# Teensy3_2_v2.net
KiCad netlist of a schematic drawn in EAGLE
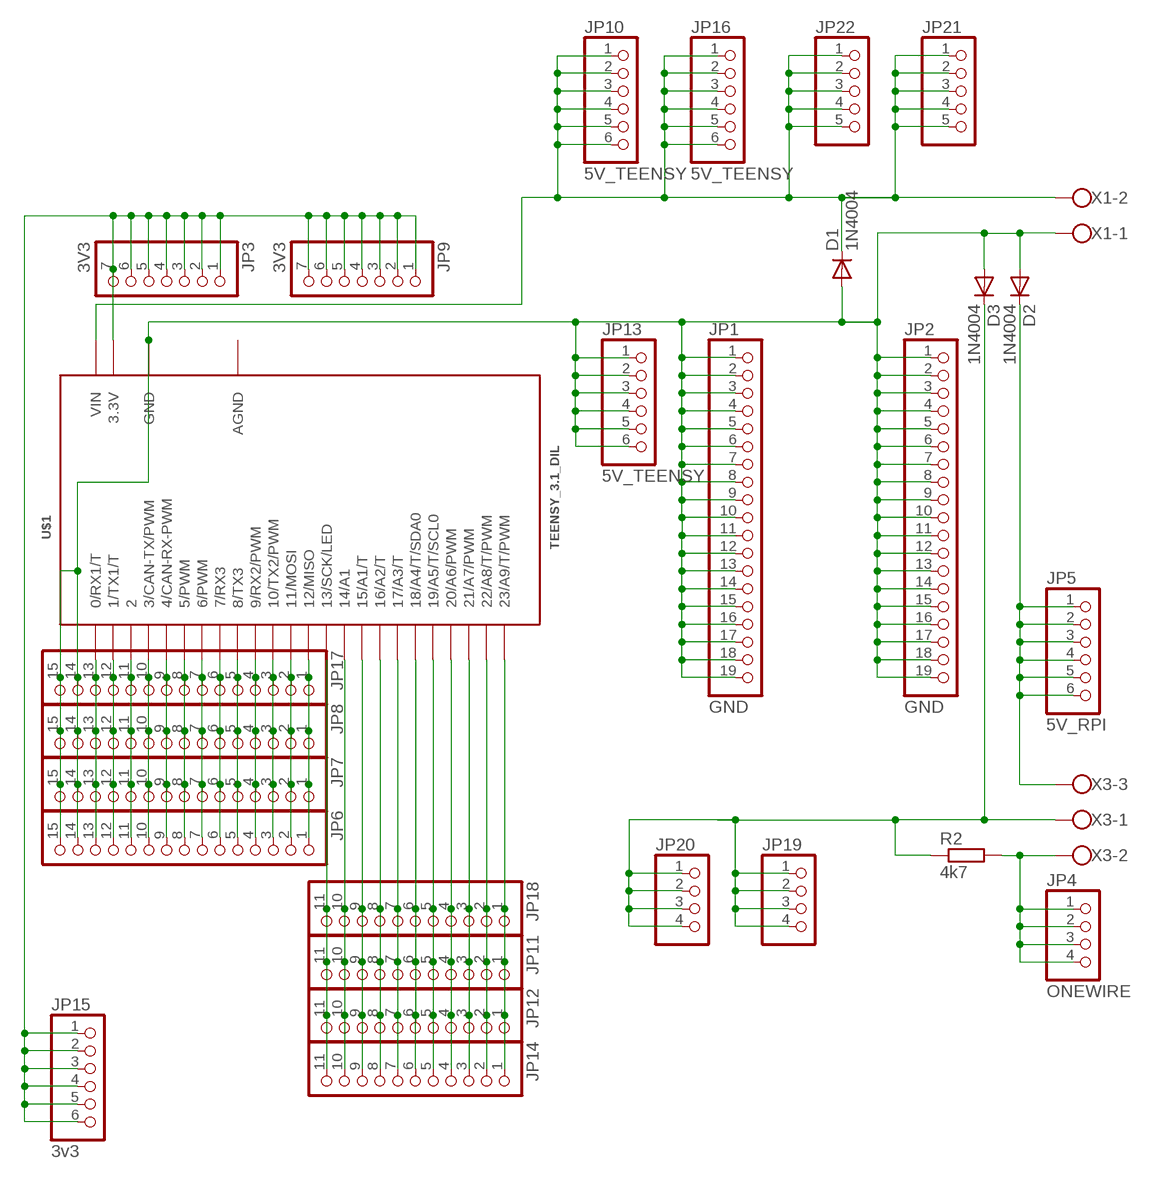
[diagram p0: schematic, sheet 1]

(export (version "E")
  (design (tool "Eeschema 10.0.6"))
  (components
    (comp (ref "D1")
      (value "1N4004")
      (footprint "eagle-import:DO41-10")
      (libsource (lib "eagle-import") (part "1N4004"))
    )
    (comp (ref "D2")
      (value "1N4004")
      (footprint "eagle-import:DO41-10")
      (libsource (lib "eagle-import") (part "1N4004"))
    )
    (comp (ref "D3")
      (value "1N4004")
      (footprint "eagle-import:DO41-10")
      (libsource (lib "eagle-import") (part "1N4004"))
    )
    (comp (ref "JP1")
      (value "GND")
      (footprint "eagle-import:1X19")
      (libsource (lib "eagle-import") (part "PINHD-1X19"))
    )
    (comp (ref "JP2")
      (value "GND")
      (footprint "eagle-import:1X19")
      (libsource (lib "eagle-import") (part "PINHD-1X19"))
    )
    (comp (ref "JP3")
      (value "3V3")
      (footprint "eagle-import:1X07")
      (libsource (lib "eagle-import") (part "PINHD-1X7"))
    )
    (comp (ref "JP4")
      (value "ONEWIRE")
      (footprint "eagle-import:1X04")
      (libsource (lib "eagle-import") (part "PINHD-1X4"))
    )
    (comp (ref "JP5")
      (value "5V_RPI")
      (footprint "eagle-import:1X06")
      (libsource (lib "eagle-import") (part "PINHD-1X6"))
    )
    (comp (ref "JP6")
      (value "PINHD-1X15")
      (footprint "eagle-import:1X15")
      (libsource (lib "eagle-import") (part "PINHD-1X15"))
    )
    (comp (ref "JP7")
      (value "PINHD-1X15")
      (footprint "eagle-import:1X15")
      (libsource (lib "eagle-import") (part "PINHD-1X15"))
    )
    (comp (ref "JP8")
      (value "PINHD-1X15")
      (footprint "eagle-import:1X15")
      (libsource (lib "eagle-import") (part "PINHD-1X15"))
    )
    (comp (ref "JP9")
      (value "3V3")
      (footprint "eagle-import:1X07")
      (libsource (lib "eagle-import") (part "PINHD-1X7"))
    )
    (comp (ref "JP10")
      (value "5V_TEENSY")
      (footprint "eagle-import:1X06")
      (libsource (lib "eagle-import") (part "PINHD-1X6"))
    )
    (comp (ref "JP11")
      (value "PINHD-1X11")
      (footprint "eagle-import:1X11")
      (libsource (lib "eagle-import") (part "PINHD-1X11"))
    )
    (comp (ref "JP12")
      (value "PINHD-1X11")
      (footprint "eagle-import:1X11")
      (libsource (lib "eagle-import") (part "PINHD-1X11"))
    )
    (comp (ref "JP13")
      (value "5V_TEENSY")
      (footprint "eagle-import:1X06")
      (libsource (lib "eagle-import") (part "PINHD-1X6"))
    )
    (comp (ref "JP14")
      (value "PINHD-1X11")
      (footprint "eagle-import:1X11")
      (libsource (lib "eagle-import") (part "PINHD-1X11"))
    )
    (comp (ref "JP15")
      (value "3v3")
      (footprint "eagle-import:1X06")
      (libsource (lib "eagle-import") (part "PINHD-1X6"))
    )
    (comp (ref "JP16")
      (value "5V_TEENSY")
      (footprint "eagle-import:1X06")
      (libsource (lib "eagle-import") (part "PINHD-1X6"))
    )
    (comp (ref "JP17")
      (value "PINHD-1X15")
      (footprint "eagle-import:1X15")
      (libsource (lib "eagle-import") (part "PINHD-1X15"))
    )
    (comp (ref "JP18")
      (value "PINHD-1X11")
      (footprint "eagle-import:1X11")
      (libsource (lib "eagle-import") (part "PINHD-1X11"))
    )
    (comp (ref "JP19")
      (value "PINHD-1X4")
      (footprint "eagle-import:1X04")
      (libsource (lib "eagle-import") (part "PINHD-1X4"))
    )
    (comp (ref "JP20")
      (value "PINHD-1X4")
      (footprint "eagle-import:1X04")
      (libsource (lib "eagle-import") (part "PINHD-1X4"))
    )
    (comp (ref "JP21")
      (value "PINHD-1X5")
      (footprint "eagle-import:1X05")
      (libsource (lib "eagle-import") (part "PINHD-1X5"))
    )
    (comp (ref "JP22")
      (value "PINHD-1X5")
      (footprint "eagle-import:1X05")
      (libsource (lib "eagle-import") (part "PINHD-1X5"))
    )
    (comp (ref "R2")
      (value "4k7")
      (footprint "eagle-import:0204_5")
      (libsource (lib "eagle-import") (part "R-EU_0204/5"))
    )
    (comp (ref "U$1")
      (value "TEENSY_3.1_DIL")
      (footprint "eagle-import:TEENSY3-DIL")
      (libsource (lib "eagle-import") (part "TEENSY_3.1_DIL"))
    )
    (comp (ref "X1")
      (value "W237-102")
      (footprint "eagle-import:W237-102")
      (fields (field (name "MPN") "237-102"))
      (libsource (lib "eagle-import") (part "W237-102"))
    )
    (comp (ref "X3")
      (value "W237-103")
      (footprint "eagle-import:W237-103")
      (fields (field (name "MPN") "237-103"))
      (libsource (lib "eagle-import") (part "W237-103"))
    )
  )
  (nets
    (net (code "1") (name "/AGND") (class "Default")
      (node (ref "U$1") (pin "AGND") (pinfunction "AGND_AGND") (pintype "power_in"))
    )
    (net (code "2") (name "Net-(JP15-Pad1)") (class "Default")
      (node (ref "JP15") (pin "1") (pinfunction "1_1") (pintype "passive"))
      (node (ref "JP15") (pin "2") (pinfunction "2_2") (pintype "passive"))
      (node (ref "JP15") (pin "3") (pinfunction "3_3") (pintype "passive"))
      (node (ref "JP15") (pin "4") (pinfunction "4_4") (pintype "passive"))
      (node (ref "JP15") (pin "5") (pinfunction "5_5") (pintype "passive"))
      (node (ref "JP15") (pin "6") (pinfunction "6_6") (pintype "passive"))
      (node (ref "JP3") (pin "1") (pinfunction "1_1") (pintype "passive"))
      (node (ref "JP3") (pin "2") (pinfunction "2_2") (pintype "passive"))
      (node (ref "JP3") (pin "3") (pinfunction "3_3") (pintype "passive"))
      (node (ref "JP3") (pin "4") (pinfunction "4_4") (pintype "passive"))
      (node (ref "JP3") (pin "5") (pinfunction "5_5") (pintype "passive"))
      (node (ref "JP3") (pin "6") (pinfunction "6_6") (pintype "passive"))
      (node (ref "JP3") (pin "7") (pinfunction "7_7") (pintype "passive"))
      (node (ref "JP9") (pin "1") (pinfunction "1_1") (pintype "passive"))
      (node (ref "JP9") (pin "2") (pinfunction "2_2") (pintype "passive"))
      (node (ref "JP9") (pin "3") (pinfunction "3_3") (pintype "passive"))
      (node (ref "JP9") (pin "4") (pinfunction "4_4") (pintype "passive"))
      (node (ref "JP9") (pin "5") (pinfunction "5_5") (pintype "passive"))
      (node (ref "JP9") (pin "6") (pinfunction "6_6") (pintype "passive"))
      (node (ref "JP9") (pin "7") (pinfunction "7_7") (pintype "passive"))
      (node (ref "U$1") (pin "3.3V") (pinfunction "3.3V_3.3V") (pintype "power_in"))
    )
    (net (code "3") (name "Net-(JP17-Pad11)") (class "Default")
      (node (ref "JP17") (pin "11") (pinfunction "11_11") (pintype "passive"))
      (node (ref "JP6") (pin "11") (pinfunction "11_11") (pintype "passive"))
      (node (ref "JP7") (pin "11") (pinfunction "11_11") (pintype "passive"))
      (node (ref "JP8") (pin "11") (pinfunction "11_11") (pintype "passive"))
      (node (ref "U$1") (pin "2") (pinfunction "2_2") (pintype "bidirectional"))
    )
    (net (code "4") (name "Net-(U$1-0{slash}RX1{slash}T)") (class "Default")
      (node (ref "JP17") (pin "13") (pinfunction "13_13") (pintype "passive"))
      (node (ref "JP6") (pin "13") (pinfunction "13_13") (pintype "passive"))
      (node (ref "JP7") (pin "13") (pinfunction "13_13") (pintype "passive"))
      (node (ref "JP8") (pin "13") (pinfunction "13_13") (pintype "passive"))
      (node (ref "U$1") (pin "0") (pinfunction "0/RX1/T_0") (pintype "bidirectional"))
    )
    (net (code "5") (name "Net-(U$1-1{slash}TX1{slash}T)") (class "Default")
      (node (ref "JP17") (pin "12") (pinfunction "12_12") (pintype "passive"))
      (node (ref "JP6") (pin "12") (pinfunction "12_12") (pintype "passive"))
      (node (ref "JP7") (pin "12") (pinfunction "12_12") (pintype "passive"))
      (node (ref "JP8") (pin "12") (pinfunction "12_12") (pintype "passive"))
      (node (ref "U$1") (pin "1") (pinfunction "1/TX1/T_1") (pintype "bidirectional"))
    )
    (net (code "6") (name "Net-(U$1-3{slash}CAN-TX{slash}PWM)") (class "Default")
      (node (ref "JP17") (pin "10") (pinfunction "10_10") (pintype "passive"))
      (node (ref "JP6") (pin "10") (pinfunction "10_10") (pintype "passive"))
      (node (ref "JP7") (pin "10") (pinfunction "10_10") (pintype "passive"))
      (node (ref "JP8") (pin "10") (pinfunction "10_10") (pintype "passive"))
      (node (ref "U$1") (pin "3") (pinfunction "3/CAN-TX/PWM_3") (pintype "bidirectional"))
    )
    (net (code "7") (name "Net-(U$1-4{slash}CAN-RX-PWM)") (class "Default")
      (node (ref "JP17") (pin "9") (pinfunction "9_9") (pintype "passive"))
      (node (ref "JP6") (pin "9") (pinfunction "9_9") (pintype "passive"))
      (node (ref "JP7") (pin "9") (pinfunction "9_9") (pintype "passive"))
      (node (ref "JP8") (pin "9") (pinfunction "9_9") (pintype "passive"))
      (node (ref "U$1") (pin "4") (pinfunction "4/CAN-RX-PWM_4") (pintype "bidirectional"))
    )
    (net (code "8") (name "Net-(U$1-5{slash}PWM)") (class "Default")
      (node (ref "JP17") (pin "8") (pinfunction "8_8") (pintype "passive"))
      (node (ref "JP6") (pin "8") (pinfunction "8_8") (pintype "passive"))
      (node (ref "JP7") (pin "8") (pinfunction "8_8") (pintype "passive"))
      (node (ref "JP8") (pin "8") (pinfunction "8_8") (pintype "passive"))
      (node (ref "U$1") (pin "5") (pinfunction "5/PWM_5") (pintype "bidirectional"))
    )
    (net (code "9") (name "Net-(U$1-6{slash}PWM)") (class "Default")
      (node (ref "JP17") (pin "7") (pinfunction "7_7") (pintype "passive"))
      (node (ref "JP6") (pin "7") (pinfunction "7_7") (pintype "passive"))
      (node (ref "JP7") (pin "7") (pinfunction "7_7") (pintype "passive"))
      (node (ref "JP8") (pin "7") (pinfunction "7_7") (pintype "passive"))
      (node (ref "U$1") (pin "6") (pinfunction "6/PWM_6") (pintype "bidirectional"))
    )
    (net (code "10") (name "Net-(U$1-7{slash}RX3)") (class "Default")
      (node (ref "JP17") (pin "6") (pinfunction "6_6") (pintype "passive"))
      (node (ref "JP6") (pin "6") (pinfunction "6_6") (pintype "passive"))
      (node (ref "JP7") (pin "6") (pinfunction "6_6") (pintype "passive"))
      (node (ref "JP8") (pin "6") (pinfunction "6_6") (pintype "passive"))
      (node (ref "U$1") (pin "7") (pinfunction "7/RX3_7") (pintype "bidirectional"))
    )
    (net (code "11") (name "Net-(U$1-8{slash}TX3)") (class "Default")
      (node (ref "JP17") (pin "5") (pinfunction "5_5") (pintype "passive"))
      (node (ref "JP6") (pin "5") (pinfunction "5_5") (pintype "passive"))
      (node (ref "JP7") (pin "5") (pinfunction "5_5") (pintype "passive"))
      (node (ref "JP8") (pin "5") (pinfunction "5_5") (pintype "passive"))
      (node (ref "U$1") (pin "8") (pinfunction "8/TX3_8") (pintype "bidirectional"))
    )
    (net (code "12") (name "Net-(U$1-9{slash}RX2{slash}PWM)") (class "Default")
      (node (ref "JP17") (pin "4") (pinfunction "4_4") (pintype "passive"))
      (node (ref "JP6") (pin "4") (pinfunction "4_4") (pintype "passive"))
      (node (ref "JP7") (pin "4") (pinfunction "4_4") (pintype "passive"))
      (node (ref "JP8") (pin "4") (pinfunction "4_4") (pintype "passive"))
      (node (ref "U$1") (pin "9") (pinfunction "9/RX2/PWM_9") (pintype "bidirectional"))
    )
    (net (code "13") (name "Net-(U$1-10{slash}TX2{slash}PWM)") (class "Default")
      (node (ref "JP17") (pin "3") (pinfunction "3_3") (pintype "passive"))
      (node (ref "JP6") (pin "3") (pinfunction "3_3") (pintype "passive"))
      (node (ref "JP7") (pin "3") (pinfunction "3_3") (pintype "passive"))
      (node (ref "JP8") (pin "3") (pinfunction "3_3") (pintype "passive"))
      (node (ref "U$1") (pin "10") (pinfunction "10/TX2/PWM_10") (pintype "bidirectional"))
    )
    (net (code "14") (name "Net-(U$1-11{slash}MOSI)") (class "Default")
      (node (ref "JP17") (pin "2") (pinfunction "2_2") (pintype "passive"))
      (node (ref "JP6") (pin "2") (pinfunction "2_2") (pintype "passive"))
      (node (ref "JP7") (pin "2") (pinfunction "2_2") (pintype "passive"))
      (node (ref "JP8") (pin "2") (pinfunction "2_2") (pintype "passive"))
      (node (ref "U$1") (pin "11") (pinfunction "11/MOSI_11") (pintype "bidirectional"))
    )
    (net (code "15") (name "Net-(U$1-12{slash}MISO)") (class "Default")
      (node (ref "JP17") (pin "1") (pinfunction "1_1") (pintype "passive"))
      (node (ref "JP6") (pin "1") (pinfunction "1_1") (pintype "passive"))
      (node (ref "JP7") (pin "1") (pinfunction "1_1") (pintype "passive"))
      (node (ref "JP8") (pin "1") (pinfunction "1_1") (pintype "passive"))
      (node (ref "U$1") (pin "12") (pinfunction "12/MISO_12") (pintype "bidirectional"))
    )
    (net (code "16") (name "Net-(U$1-13{slash}SCK{slash}LED)") (class "Default")
      (node (ref "JP11") (pin "11") (pinfunction "11_11") (pintype "passive"))
      (node (ref "JP12") (pin "11") (pinfunction "11_11") (pintype "passive"))
      (node (ref "JP14") (pin "11") (pinfunction "11_11") (pintype "passive"))
      (node (ref "JP18") (pin "11") (pinfunction "11_11") (pintype "passive"))
      (node (ref "U$1") (pin "13") (pinfunction "13/SCK/LED_13") (pintype "bidirectional"))
    )
    (net (code "17") (name "Net-(U$1-14{slash}A1)") (class "Default")
      (node (ref "JP11") (pin "10") (pinfunction "10_10") (pintype "passive"))
      (node (ref "JP12") (pin "10") (pinfunction "10_10") (pintype "passive"))
      (node (ref "JP14") (pin "10") (pinfunction "10_10") (pintype "passive"))
      (node (ref "JP18") (pin "10") (pinfunction "10_10") (pintype "passive"))
      (node (ref "U$1") (pin "14/A0") (pinfunction "14/A1_14/A0") (pintype "bidirectional"))
    )
    (net (code "18") (name "Net-(U$1-15{slash}A1{slash}T)") (class "Default")
      (node (ref "JP11") (pin "9") (pinfunction "9_9") (pintype "passive"))
      (node (ref "JP12") (pin "9") (pinfunction "9_9") (pintype "passive"))
      (node (ref "JP14") (pin "9") (pinfunction "9_9") (pintype "passive"))
      (node (ref "JP18") (pin "9") (pinfunction "9_9") (pintype "passive"))
      (node (ref "U$1") (pin "15/A1") (pinfunction "15/A1/T_15/A1") (pintype "bidirectional"))
    )
    (net (code "19") (name "Net-(U$1-16{slash}A2{slash}T)") (class "Default")
      (node (ref "JP11") (pin "8") (pinfunction "8_8") (pintype "passive"))
      (node (ref "JP12") (pin "8") (pinfunction "8_8") (pintype "passive"))
      (node (ref "JP14") (pin "8") (pinfunction "8_8") (pintype "passive"))
      (node (ref "JP18") (pin "8") (pinfunction "8_8") (pintype "passive"))
      (node (ref "U$1") (pin "16/A2") (pinfunction "16/A2/T_16/A2") (pintype "bidirectional"))
    )
    (net (code "20") (name "Net-(U$1-17{slash}A3{slash}T)") (class "Default")
      (node (ref "JP11") (pin "7") (pinfunction "7_7") (pintype "passive"))
      (node (ref "JP12") (pin "7") (pinfunction "7_7") (pintype "passive"))
      (node (ref "JP14") (pin "7") (pinfunction "7_7") (pintype "passive"))
      (node (ref "JP18") (pin "7") (pinfunction "7_7") (pintype "passive"))
      (node (ref "U$1") (pin "17/A3") (pinfunction "17/A3/T_17/A3") (pintype "bidirectional"))
    )
    (net (code "21") (name "Net-(U$1-18{slash}A4{slash}T{slash}SDA0)") (class "Default")
      (node (ref "JP11") (pin "6") (pinfunction "6_6") (pintype "passive"))
      (node (ref "JP12") (pin "6") (pinfunction "6_6") (pintype "passive"))
      (node (ref "JP14") (pin "6") (pinfunction "6_6") (pintype "passive"))
      (node (ref "JP18") (pin "6") (pinfunction "6_6") (pintype "passive"))
      (node (ref "U$1") (pin "18/A4") (pinfunction "18/A4/T/SDA0_18/A4") (pintype "bidirectional"))
    )
    (net (code "22") (name "Net-(U$1-19{slash}A5{slash}T{slash}SCL0)") (class "Default")
      (node (ref "JP11") (pin "5") (pinfunction "5_5") (pintype "passive"))
      (node (ref "JP12") (pin "5") (pinfunction "5_5") (pintype "passive"))
      (node (ref "JP14") (pin "5") (pinfunction "5_5") (pintype "passive"))
      (node (ref "JP18") (pin "5") (pinfunction "5_5") (pintype "passive"))
      (node (ref "U$1") (pin "19/A5") (pinfunction "19/A5/T/SCL0_19/A5") (pintype "bidirectional"))
    )
    (net (code "23") (name "Net-(U$1-20{slash}A6{slash}PWM)") (class "Default")
      (node (ref "JP11") (pin "4") (pinfunction "4_4") (pintype "passive"))
      (node (ref "JP12") (pin "4") (pinfunction "4_4") (pintype "passive"))
      (node (ref "JP14") (pin "4") (pinfunction "4_4") (pintype "passive"))
      (node (ref "JP18") (pin "4") (pinfunction "4_4") (pintype "passive"))
      (node (ref "U$1") (pin "20/A6") (pinfunction "20/A6/PWM_20/A6") (pintype "bidirectional"))
    )
    (net (code "24") (name "Net-(U$1-21{slash}A7{slash}PWM)") (class "Default")
      (node (ref "JP11") (pin "3") (pinfunction "3_3") (pintype "passive"))
      (node (ref "JP12") (pin "3") (pinfunction "3_3") (pintype "passive"))
      (node (ref "JP14") (pin "3") (pinfunction "3_3") (pintype "passive"))
      (node (ref "JP18") (pin "3") (pinfunction "3_3") (pintype "passive"))
      (node (ref "U$1") (pin "21/A7") (pinfunction "21/A7/PWM_21/A7") (pintype "bidirectional"))
    )
    (net (code "25") (name "Net-(U$1-22{slash}A8{slash}T{slash}PWM)") (class "Default")
      (node (ref "JP11") (pin "2") (pinfunction "2_2") (pintype "passive"))
      (node (ref "JP12") (pin "2") (pinfunction "2_2") (pintype "passive"))
      (node (ref "JP14") (pin "2") (pinfunction "2_2") (pintype "passive"))
      (node (ref "JP18") (pin "2") (pinfunction "2_2") (pintype "passive"))
      (node (ref "U$1") (pin "22/A8") (pinfunction "22/A8/T/PWM_22/A8") (pintype "bidirectional"))
    )
    (net (code "26") (name "Net-(U$1-23{slash}A9{slash}T{slash}PWM)") (class "Default")
      (node (ref "JP11") (pin "1") (pinfunction "1_1") (pintype "passive"))
      (node (ref "JP12") (pin "1") (pinfunction "1_1") (pintype "passive"))
      (node (ref "JP14") (pin "1") (pinfunction "1_1") (pintype "passive"))
      (node (ref "JP18") (pin "1") (pinfunction "1_1") (pintype "passive"))
      (node (ref "U$1") (pin "23/A9") (pinfunction "23/A9/T/PWM_23/A9") (pintype "bidirectional"))
    )
    (net (code "27") (name "Net-(X1A-KL)") (class "Default")
      (node (ref "D1") (pin "A") (pinfunction "A_A") (pintype "passive"))
      (node (ref "D2") (pin "A") (pinfunction "A_A") (pintype "passive"))
      (node (ref "D3") (pin "A") (pinfunction "A_A") (pintype "passive"))
      (node (ref "JP1") (pin "1") (pinfunction "1_1") (pintype "passive"))
      (node (ref "JP1") (pin "10") (pinfunction "10_10") (pintype "passive"))
      (node (ref "JP1") (pin "11") (pinfunction "11_11") (pintype "passive"))
      (node (ref "JP1") (pin "12") (pinfunction "12_12") (pintype "passive"))
      (node (ref "JP1") (pin "13") (pinfunction "13_13") (pintype "passive"))
      (node (ref "JP1") (pin "14") (pinfunction "14_14") (pintype "passive"))
      (node (ref "JP1") (pin "15") (pinfunction "15_15") (pintype "passive"))
      (node (ref "JP1") (pin "16") (pinfunction "16_16") (pintype "passive"))
      (node (ref "JP1") (pin "17") (pinfunction "17_17") (pintype "passive"))
      (node (ref "JP1") (pin "18") (pinfunction "18_18") (pintype "passive"))
      (node (ref "JP1") (pin "19") (pinfunction "19_19") (pintype "passive"))
      (node (ref "JP1") (pin "2") (pinfunction "2_2") (pintype "passive"))
      (node (ref "JP1") (pin "3") (pinfunction "3_3") (pintype "passive"))
      (node (ref "JP1") (pin "4") (pinfunction "4_4") (pintype "passive"))
      (node (ref "JP1") (pin "5") (pinfunction "5_5") (pintype "passive"))
      (node (ref "JP1") (pin "6") (pinfunction "6_6") (pintype "passive"))
      (node (ref "JP1") (pin "7") (pinfunction "7_7") (pintype "passive"))
      (node (ref "JP1") (pin "8") (pinfunction "8_8") (pintype "passive"))
      (node (ref "JP1") (pin "9") (pinfunction "9_9") (pintype "passive"))
      (node (ref "JP13") (pin "1") (pinfunction "1_1") (pintype "passive"))
      (node (ref "JP13") (pin "2") (pinfunction "2_2") (pintype "passive"))
      (node (ref "JP13") (pin "3") (pinfunction "3_3") (pintype "passive"))
      (node (ref "JP13") (pin "4") (pinfunction "4_4") (pintype "passive"))
      (node (ref "JP13") (pin "5") (pinfunction "5_5") (pintype "passive"))
      (node (ref "JP13") (pin "6") (pinfunction "6_6") (pintype "passive"))
      (node (ref "JP17") (pin "14") (pinfunction "14_14") (pintype "passive"))
      (node (ref "JP17") (pin "15") (pinfunction "15_15") (pintype "passive"))
      (node (ref "JP2") (pin "1") (pinfunction "1_1") (pintype "passive"))
      (node (ref "JP2") (pin "10") (pinfunction "10_10") (pintype "passive"))
      (node (ref "JP2") (pin "11") (pinfunction "11_11") (pintype "passive"))
      (node (ref "JP2") (pin "12") (pinfunction "12_12") (pintype "passive"))
      (node (ref "JP2") (pin "13") (pinfunction "13_13") (pintype "passive"))
      (node (ref "JP2") (pin "14") (pinfunction "14_14") (pintype "passive"))
      (node (ref "JP2") (pin "15") (pinfunction "15_15") (pintype "passive"))
      (node (ref "JP2") (pin "16") (pinfunction "16_16") (pintype "passive"))
      (node (ref "JP2") (pin "17") (pinfunction "17_17") (pintype "passive"))
      (node (ref "JP2") (pin "18") (pinfunction "18_18") (pintype "passive"))
      (node (ref "JP2") (pin "19") (pinfunction "19_19") (pintype "passive"))
      (node (ref "JP2") (pin "2") (pinfunction "2_2") (pintype "passive"))
      (node (ref "JP2") (pin "3") (pinfunction "3_3") (pintype "passive"))
      (node (ref "JP2") (pin "4") (pinfunction "4_4") (pintype "passive"))
      (node (ref "JP2") (pin "5") (pinfunction "5_5") (pintype "passive"))
      (node (ref "JP2") (pin "6") (pinfunction "6_6") (pintype "passive"))
      (node (ref "JP2") (pin "7") (pinfunction "7_7") (pintype "passive"))
      (node (ref "JP2") (pin "8") (pinfunction "8_8") (pintype "passive"))
      (node (ref "JP2") (pin "9") (pinfunction "9_9") (pintype "passive"))
      (node (ref "JP6") (pin "14") (pinfunction "14_14") (pintype "passive"))
      (node (ref "JP6") (pin "15") (pinfunction "15_15") (pintype "passive"))
      (node (ref "JP7") (pin "14") (pinfunction "14_14") (pintype "passive"))
      (node (ref "JP7") (pin "15") (pinfunction "15_15") (pintype "passive"))
      (node (ref "JP8") (pin "14") (pinfunction "14_14") (pintype "passive"))
      (node (ref "JP8") (pin "15") (pinfunction "15_15") (pintype "passive"))
      (node (ref "U$1") (pin "GND") (pinfunction "GND_GND") (pintype "power_in"))
      (node (ref "X1") (pin "1") (pinfunction "KL_1") (pintype "passive"))
    )
    (net (code "28") (name "Net-(X1B-KL)") (class "Default")
      (node (ref "D1") (pin "C") (pinfunction "C_C") (pintype "passive"))
      (node (ref "JP10") (pin "1") (pinfunction "1_1") (pintype "passive"))
      (node (ref "JP10") (pin "2") (pinfunction "2_2") (pintype "passive"))
      (node (ref "JP10") (pin "3") (pinfunction "3_3") (pintype "passive"))
      (node (ref "JP10") (pin "4") (pinfunction "4_4") (pintype "passive"))
      (node (ref "JP10") (pin "5") (pinfunction "5_5") (pintype "passive"))
      (node (ref "JP10") (pin "6") (pinfunction "6_6") (pintype "passive"))
      (node (ref "JP16") (pin "1") (pinfunction "1_1") (pintype "passive"))
      (node (ref "JP16") (pin "2") (pinfunction "2_2") (pintype "passive"))
      (node (ref "JP16") (pin "3") (pinfunction "3_3") (pintype "passive"))
      (node (ref "JP16") (pin "4") (pinfunction "4_4") (pintype "passive"))
      (node (ref "JP16") (pin "5") (pinfunction "5_5") (pintype "passive"))
      (node (ref "JP16") (pin "6") (pinfunction "6_6") (pintype "passive"))
      (node (ref "JP21") (pin "1") (pinfunction "1_1") (pintype "passive"))
      (node (ref "JP21") (pin "2") (pinfunction "2_2") (pintype "passive"))
      (node (ref "JP21") (pin "3") (pinfunction "3_3") (pintype "passive"))
      (node (ref "JP21") (pin "4") (pinfunction "4_4") (pintype "passive"))
      (node (ref "JP21") (pin "5") (pinfunction "5_5") (pintype "passive"))
      (node (ref "JP22") (pin "1") (pinfunction "1_1") (pintype "passive"))
      (node (ref "JP22") (pin "2") (pinfunction "2_2") (pintype "passive"))
      (node (ref "JP22") (pin "3") (pinfunction "3_3") (pintype "passive"))
      (node (ref "JP22") (pin "4") (pinfunction "4_4") (pintype "passive"))
      (node (ref "JP22") (pin "5") (pinfunction "5_5") (pintype "passive"))
      (node (ref "U$1") (pin "VIN") (pinfunction "VIN_VIN") (pintype "power_in"))
      (node (ref "X1") (pin "2") (pinfunction "KL_2") (pintype "passive"))
    )
    (net (code "29") (name "Net-(X3A-KL)") (class "Default")
      (node (ref "D3") (pin "C") (pinfunction "C_C") (pintype "passive"))
      (node (ref "JP19") (pin "1") (pinfunction "1_1") (pintype "passive"))
      (node (ref "JP19") (pin "2") (pinfunction "2_2") (pintype "passive"))
      (node (ref "JP19") (pin "3") (pinfunction "3_3") (pintype "passive"))
      (node (ref "JP19") (pin "4") (pinfunction "4_4") (pintype "passive"))
      (node (ref "JP20") (pin "1") (pinfunction "1_1") (pintype "passive"))
      (node (ref "JP20") (pin "2") (pinfunction "2_2") (pintype "passive"))
      (node (ref "JP20") (pin "3") (pinfunction "3_3") (pintype "passive"))
      (node (ref "JP20") (pin "4") (pinfunction "4_4") (pintype "passive"))
      (node (ref "R2") (pin "1") (pinfunction "1_1") (pintype "passive"))
      (node (ref "X3") (pin "1") (pinfunction "KL_1") (pintype "passive"))
    )
    (net (code "30") (name "Net-(X3B-KL)") (class "Default")
      (node (ref "JP4") (pin "1") (pinfunction "1_1") (pintype "passive"))
      (node (ref "JP4") (pin "2") (pinfunction "2_2") (pintype "passive"))
      (node (ref "JP4") (pin "3") (pinfunction "3_3") (pintype "passive"))
      (node (ref "JP4") (pin "4") (pinfunction "4_4") (pintype "passive"))
      (node (ref "R2") (pin "2") (pinfunction "2_2") (pintype "passive"))
      (node (ref "X3") (pin "2") (pinfunction "KL_2") (pintype "passive"))
    )
    (net (code "31") (name "Net-(X3C-KL)") (class "Default")
      (node (ref "D2") (pin "C") (pinfunction "C_C") (pintype "passive"))
      (node (ref "JP5") (pin "1") (pinfunction "1_1") (pintype "passive"))
      (node (ref "JP5") (pin "2") (pinfunction "2_2") (pintype "passive"))
      (node (ref "JP5") (pin "3") (pinfunction "3_3") (pintype "passive"))
      (node (ref "JP5") (pin "4") (pinfunction "4_4") (pintype "passive"))
      (node (ref "JP5") (pin "5") (pinfunction "5_5") (pintype "passive"))
      (node (ref "JP5") (pin "6") (pinfunction "6_6") (pintype "passive"))
      (node (ref "X3") (pin "3") (pinfunction "KL_3") (pintype "passive"))
    )
  )
)
